# poe.net
KiCad netlist of a schematic drawn in Altium Designer
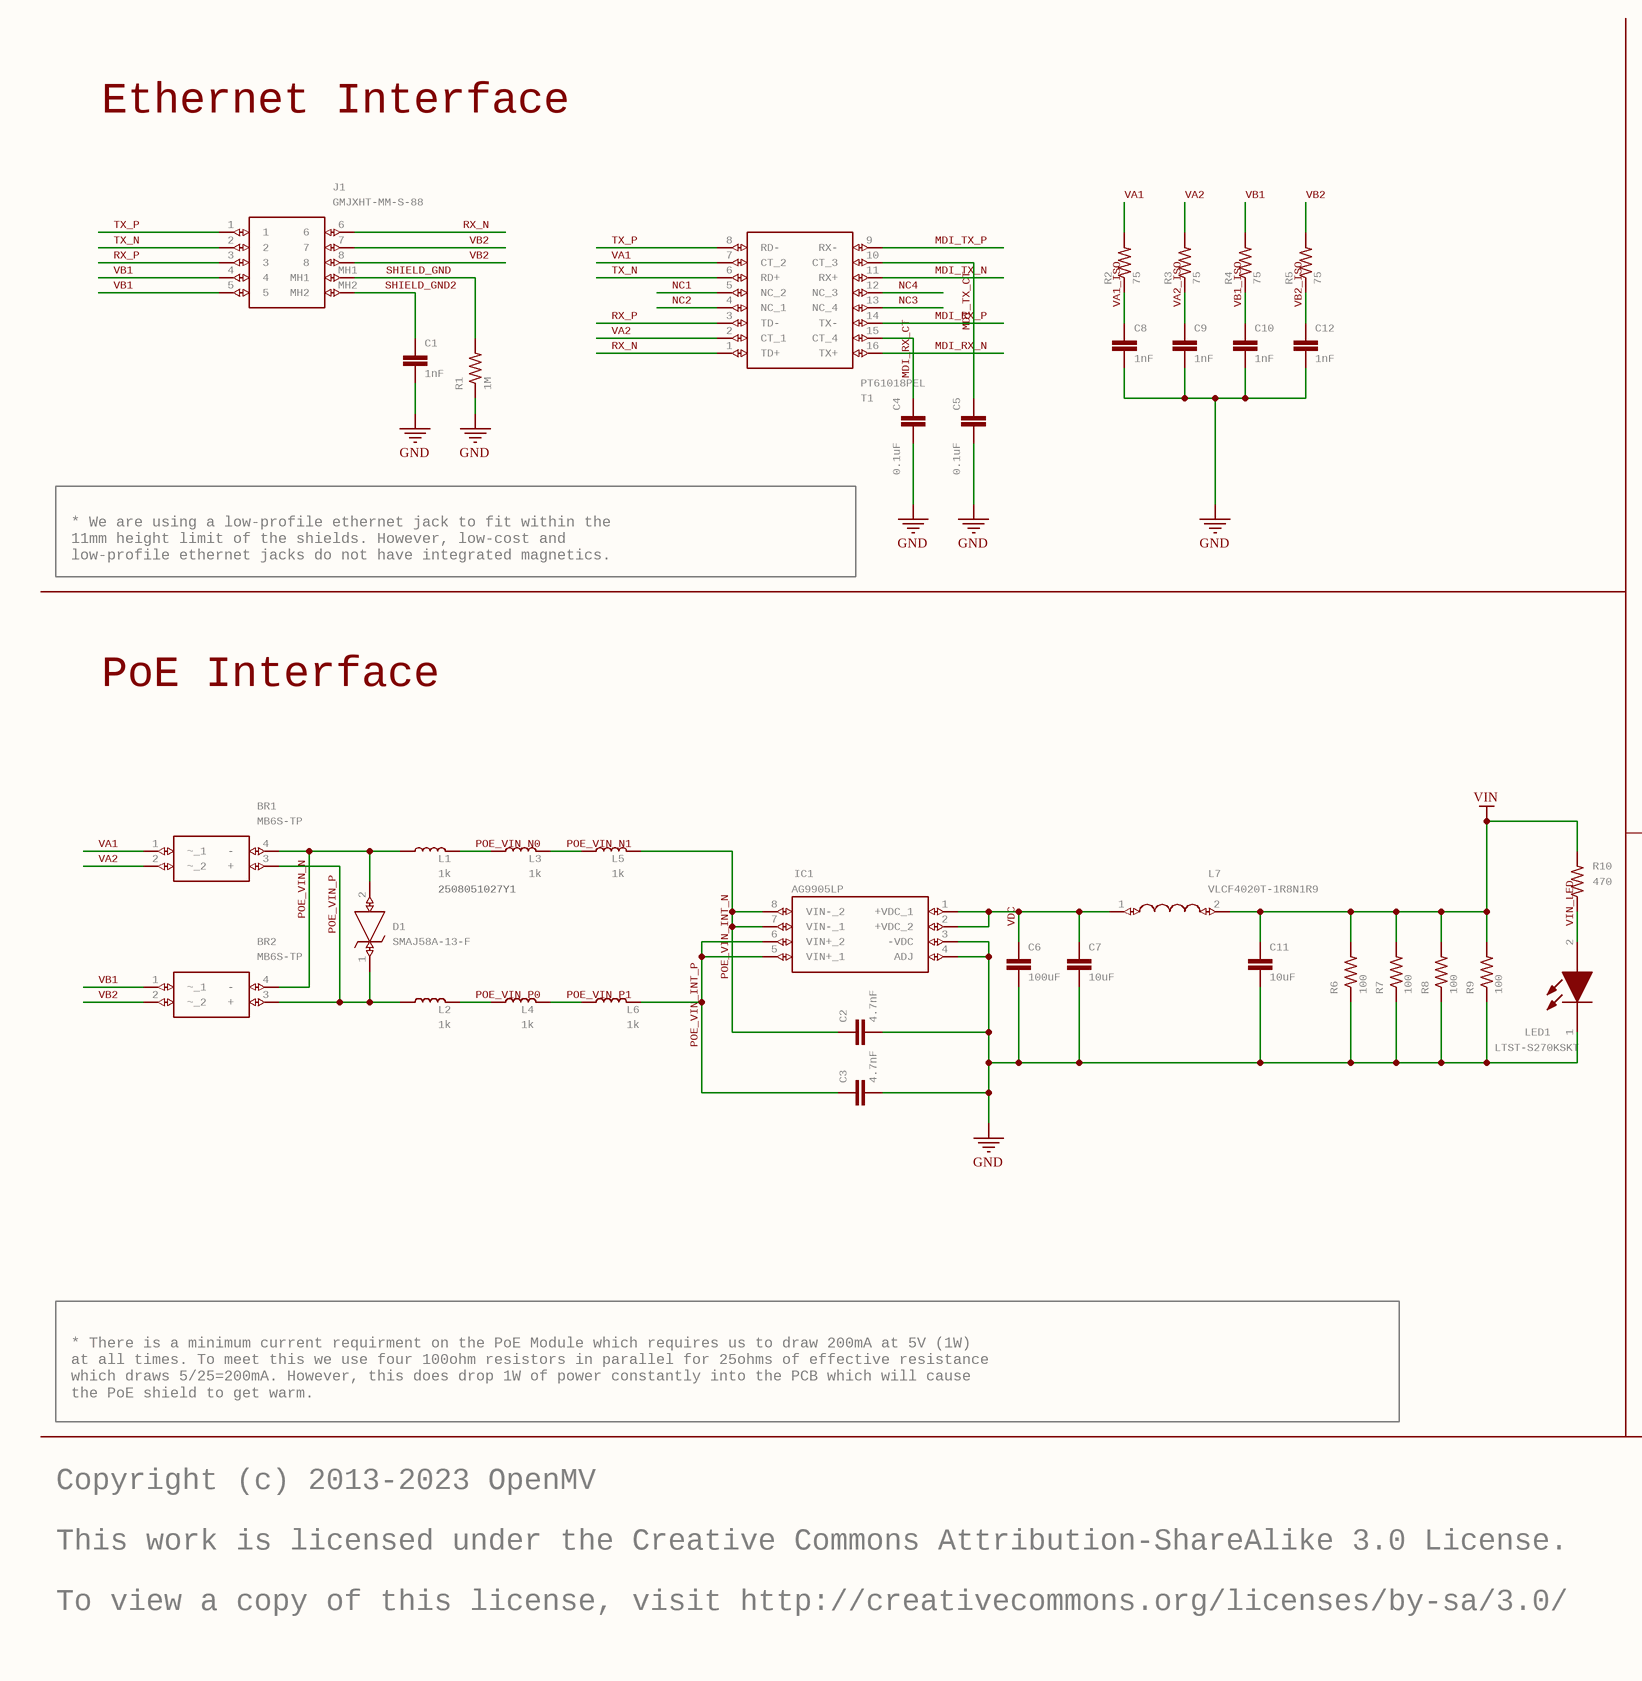
[diagram p0: poe.SchDoc, left]
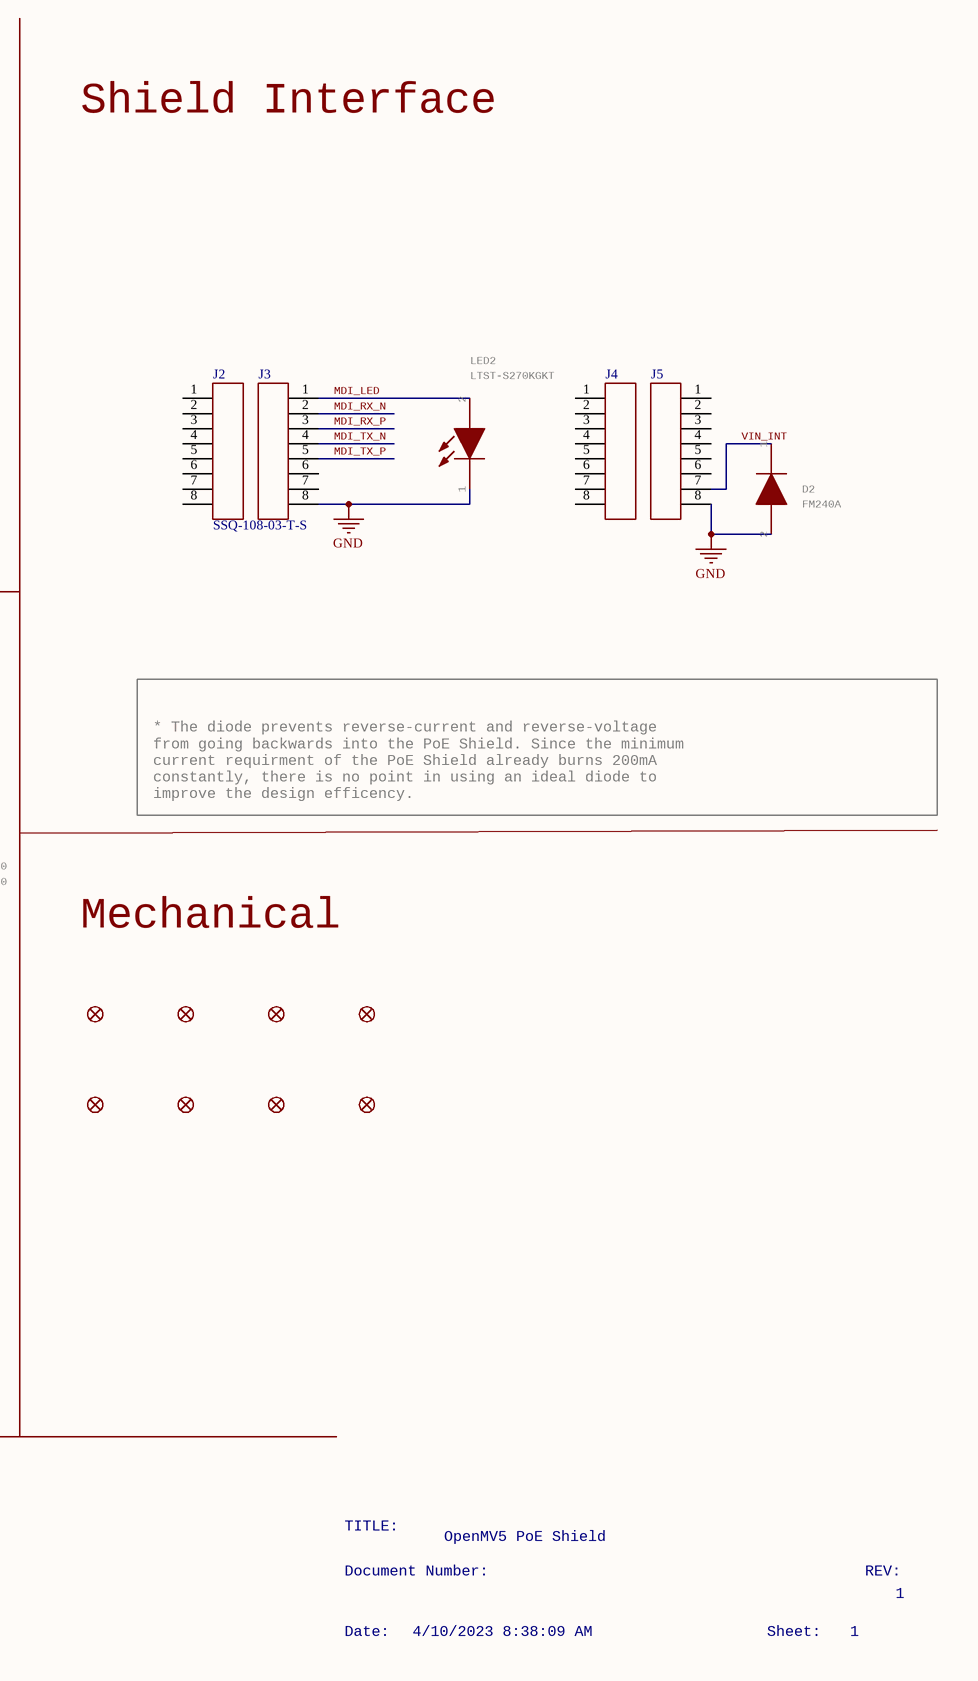
[diagram p1: poe.SchDoc, right]

(export (version "E")
  (design (tool "Eeschema 10.0.6"))
  (components
    (comp (ref "BR1")
      (value "MB6S-TP")
      (footprint "SOP254P665X270-4N")
      (description "MICRO COMMERCIAL COMPONENTS - MB6S-TP - BRIDGE RECTIFIER, 500mA, 600V   Source:  Datasheet")
      (fields (field (name "MOUSER_PART_NUMBER") "833-MB6S-TP"))
      (libsource (lib "poe") (part "MB6S-TP"))
    )
    (comp (ref "BR2")
      (value "MB6S-TP")
      (footprint "SOP254P665X270-4N")
      (description "MICRO COMMERCIAL COMPONENTS - MB6S-TP - BRIDGE RECTIFIER, 500mA, 600V   Source:  Datasheet")
      (fields (field (name "MOUSER_PART_NUMBER") "833-MB6S-TP"))
      (libsource (lib "poe") (part "MB6S-TP"))
    )
    (comp (ref "C1")
      (value "1nF")
      (footprint "C1206")
      (description "CAPACITOR, European symbol")
      (fields (field (name "MPN") "1206B102K252CT"))
      (libsource (lib "poe") (part "C-EUC1206"))
    )
    (comp (ref "C2")
      (value "4.7nF")
      (footprint "C1812")
      (description "CAPACITOR, European symbol")
      (fields (field (name "MPN") "202S43W472KV4E"))
      (libsource (lib "poe") (part "C-EUC1812"))
    )
    (comp (ref "C3")
      (value "4.7nF")
      (footprint "C1812")
      (description "CAPACITOR, European symbol")
      (fields (field (name "MPN") "202S43W472KV4E"))
      (libsource (lib "poe") (part "C-EUC1812"))
    )
    (comp (ref "C4")
      (value "0.1uF")
      (footprint "C0402")
      (description "CAPACITOR, European symbol")
      (fields (field (name "MPN") "GRM155R71H104KE14D"))
      (libsource (lib "poe") (part "C-EUC0201"))
    )
    (comp (ref "C5")
      (value "0.1uF")
      (footprint "C0402")
      (description "CAPACITOR, European symbol")
      (fields (field (name "MPN") "GRM155R71H104KE14D"))
      (libsource (lib "poe") (part "C-EUC0201"))
    )
    (comp (ref "C6")
      (value "100uF")
      (footprint "C1206")
      (description "CAPACITOR, European symbol")
      (fields (field (name "MPN") "CL31A107MQHNNWE"))
      (libsource (lib "poe") (part "C-EUC1206"))
    )
    (comp (ref "C7")
      (value "10uF")
      (footprint "C0402")
      (description "CAPACITOR, European symbol")
      (fields (field (name "MPN") "GRM155R60J106ME05D"))
      (libsource (lib "poe") (part "C-EUC0402"))
    )
    (comp (ref "C8")
      (value "1nF")
      (footprint "C1206")
      (description "CAPACITOR, European symbol")
      (fields (field (name "MPN") "1206B102K252CT"))
      (libsource (lib "poe") (part "C-EUC1206"))
    )
    (comp (ref "C9")
      (value "1nF")
      (footprint "C1206")
      (description "CAPACITOR, European symbol")
      (fields (field (name "MPN") "1206B102K252CT"))
      (libsource (lib "poe") (part "C-EUC1206"))
    )
    (comp (ref "C10")
      (value "1nF")
      (footprint "C1206")
      (description "CAPACITOR, European symbol")
      (fields (field (name "MPN") "1206B102K252CT"))
      (libsource (lib "poe") (part "C-EUC1206"))
    )
    (comp (ref "C11")
      (value "10uF")
      (footprint "C0402")
      (description "CAPACITOR, European symbol")
      (fields (field (name "MPN") "GRM155R60J106ME05D"))
      (libsource (lib "poe") (part "C-EUC0402"))
    )
    (comp (ref "C12")
      (value "1nF")
      (footprint "C1206")
      (description "CAPACITOR, European symbol")
      (fields (field (name "MPN") "1206B102K252CT"))
      (libsource (lib "poe") (part "C-EUC1206"))
    )
    (comp (ref "D1")
      (value "SMAJ58A-13-F")
      (footprint "DIOM5226X230N")
      (description "Diodes Inc SMAJ58A-13-F, Uni-Directional TVS Diode, 400W, 2-Pin DO-214AC   Source:  Datasheet")
      (fields (field (name "MOUSER_PART_NUMBER") "621-SMAJ58A-13-F") (field (name "MPN") "SMAJ58A/TR13"))
      (libsource (lib "poe") (part "SMAJ58A-13-F"))
    )
    (comp (ref "D2")
      (value "FM240A")
      (footprint "DIOM5025X231N")
      (description "Diodes - General Purpose, Power, Switching GP Si Rectifier SMB,2A,40V   Source:  Datasheet")
      (fields (field (name "MOUSER_PART_NUMBER") "583-FM240A"))
      (libsource (lib "poe") (part "FM240A"))
    )
    (comp (ref "FD1")
      (value "FIDUCIAL1X2")
      (footprint "FIDUCIAL-1X2")
      (fields (field (name "LIBRARYNAME") "SparkFun-Aesthetics"))
      (libsource (lib "poe") (part "FIDUCIAL1X2"))
    )
    (comp (ref "FD2")
      (value "FIDUCIAL1X2")
      (footprint "FIDUCIAL-1X2")
      (fields (field (name "LIBRARYNAME") "SparkFun-Aesthetics"))
      (libsource (lib "poe") (part "FIDUCIAL1X2"))
    )
    (comp (ref "FD3")
      (value "FIDUCIAL1X2")
      (footprint "FIDUCIAL-1X2")
      (fields (field (name "LIBRARYNAME") "SparkFun-Aesthetics"))
      (libsource (lib "poe") (part "FIDUCIAL1X2"))
    )
    (comp (ref "FD4")
      (value "FIDUCIAL1X2")
      (footprint "FIDUCIAL-1X2")
      (fields (field (name "LIBRARYNAME") "SparkFun-Aesthetics"))
      (libsource (lib "poe") (part "FIDUCIAL1X2"))
    )
    (comp (ref "FD5")
      (value "FIDUCIAL1X2")
      (footprint "FIDUCIAL-1X2")
      (fields (field (name "LIBRARYNAME") "SparkFun-Aesthetics"))
      (libsource (lib "poe") (part "FIDUCIAL1X2"))
    )
    (comp (ref "FD6")
      (value "FIDUCIAL1X2")
      (footprint "FIDUCIAL-1X2")
      (fields (field (name "LIBRARYNAME") "SparkFun-Aesthetics"))
      (libsource (lib "poe") (part "FIDUCIAL1X2"))
    )
    (comp (ref "FD7")
      (value "FIDUCIAL1X2")
      (footprint "FIDUCIAL-1X2")
      (fields (field (name "LIBRARYNAME") "SparkFun-Aesthetics"))
      (libsource (lib "poe") (part "FIDUCIAL1X2"))
    )
    (comp (ref "FD8")
      (value "FIDUCIAL1X2")
      (footprint "FIDUCIAL-1X2")
      (fields (field (name "LIBRARYNAME") "SparkFun-Aesthetics"))
      (libsource (lib "poe") (part "FIDUCIAL1X2"))
    )
    (comp (ref "IC1")
      (value "AG9905LP")
      (footprint "AG9905LP")
      (description "Power Management Modules IEEE802.3af PD module. 5V 7W, low profile   Source:  Datasheet")
      (fields
        (field (name "MANUFACTURER_PART_NUMBER") "Ag9905LP")
        (field (name "MOUSER_PART_NUMBER") "480-AG9905LP")
      )
      (libsource (lib "poe") (part "AG9905LP"))
    )
    (comp (ref "J1")
      (value "GMJXHT-MM-S-88")
      (footprint "GMJXHTMMS88")
      (description "MODJACK MIDMOUNT 8P8C SHIELD RoHS COMPLIANT   Source:  Datasheet")
      (fields (field (name "MOUSER_PART_NUMBER") "806-GMJXHT-MM-S-88"))
      (libsource (lib "poe") (part "GMJXHT-MM-S-88"))
    )
    (comp (ref "J2") (value "SSQ-108-03-T-S") (footprint "HDR_1X8") (libsource (lib "") (part "HDR_1X8_1")))
    (comp (ref "J3") (value "SSQ-108-03-T-S") (footprint "HDR_1X8") (libsource (lib "pir") (part "HDR_1X8")))
    (comp (ref "J4") (value "SSQ-108-03-T-S") (footprint "HDR_1X8") (libsource (lib "") (part "HDR_1X8_1")))
    (comp (ref "J5") (value "SSQ-108-03-T-S") (footprint "HDR_1X8") (libsource (lib "pir") (part "HDR_1X8")))
    (comp (ref "L1")
      (value "1k")
      (footprint "R0805")
      (fields
        (field (name "MPN") "2508051027Y1")
        (field (name "PART NUMBER") "2508051027Y1")
        (field (name "LIBRARYNAME") "SparkFun-Coils")
      )
      (libsource (lib "poe") (part "INDUCTOR-0402-3.9NH"))
    )
    (comp (ref "L2")
      (value "1k")
      (footprint "R0805")
      (fields (field (name "MPN") "2508051027Y1") (field (name "LIBRARYNAME") "SparkFun-Coils"))
      (libsource (lib "poe") (part "INDUCTOR-0402-3.9NH"))
    )
    (comp (ref "L3")
      (value "1k")
      (footprint "R0805")
      (fields (field (name "MPN") "2508051027Y1") (field (name "LIBRARYNAME") "SparkFun-Coils"))
      (libsource (lib "poe") (part "INDUCTOR-0402-3.9NH"))
    )
    (comp (ref "L4")
      (value "1k")
      (footprint "R0805")
      (fields (field (name "MPN") "2508051027Y1") (field (name "LIBRARYNAME") "SparkFun-Coils"))
      (libsource (lib "poe") (part "INDUCTOR-0402-3.9NH"))
    )
    (comp (ref "L5")
      (value "1k")
      (footprint "R0805")
      (fields (field (name "MPN") "2508051027Y1") (field (name "LIBRARYNAME") "SparkFun-Coils"))
      (libsource (lib "poe") (part "INDUCTOR-0402-3.9NH"))
    )
    (comp (ref "L6")
      (value "1k")
      (footprint "R0805")
      (fields (field (name "MPN") "2508051027Y1") (field (name "LIBRARYNAME") "SparkFun-Coils"))
      (libsource (lib "poe") (part "INDUCTOR-0402-3.9NH"))
    )
    (comp (ref "L7")
      (value "VLCF4020T-1R8N1R9")
      (footprint "VLCF4020T-1R8N1R9")
      (description "Power Inductors - SMD 1.8uH 1.9A 4x4x2.0mm")
      (libsource (lib "poe") (part "NR6045T1R8N"))
    )
    (comp (ref "LED1")
      (value "LTST-S270KSKT")
      (footprint "LTSTS270K")
      (fields (field (name "MOUSER_PART_NUMBER") "859-LTST-S270KSKT"))
      (libsource (lib "poe") (part "LTST-S270KSKT"))
    )
    (comp (ref "LED2")
      (value "LTST-S270KGKT")
      (footprint "LTSTS270K")
      (fields (field (name "MOUSER_PART_NUMBER") "859-LTST-S270KGKT"))
      (libsource (lib "poe") (part "LTST-S270KGKT"))
    )
    (comp (ref "R1")
      (value "1M")
      (footprint "R1206")
      (description "RESISTOR, American symbol")
      (fields (field (name "MPN") "RMCF1206FT1M00"))
      (libsource (lib "poe") (part "R-US_R1206"))
    )
    (comp (ref "R2")
      (value "75")
      (footprint "R0402")
      (description "RESISTOR, American symbol")
      (fields (field (name "MPN") "CR0402-FX-75R0GLF"))
      (libsource (lib "poe") (part "R-US_R0402"))
    )
    (comp (ref "R3")
      (value "75")
      (footprint "R0402")
      (description "RESISTOR, American symbol")
      (fields (field (name "MPN") "CR0402-FX-75R0GLF"))
      (libsource (lib "poe") (part "R-US_R0402"))
    )
    (comp (ref "R4")
      (value "75")
      (footprint "R0402")
      (description "RESISTOR, American symbol")
      (fields (field (name "MPN") "CR0402-FX-75R0GLF"))
      (libsource (lib "poe") (part "R-US_R0402"))
    )
    (comp (ref "R5")
      (value "75")
      (footprint "R0402")
      (description "RESISTOR, American symbol")
      (fields (field (name "MPN") "CR0402-FX-75R0GLF"))
      (libsource (lib "poe") (part "R-US_R0402"))
    )
    (comp (ref "R6")
      (value "100")
      (footprint "R2512")
      (description "RESISTOR, American symbol")
      (fields (field (name "MPN") "RC2512JK-07100RL"))
      (libsource (lib "poe") (part "R-US_R2512"))
    )
    (comp (ref "R7")
      (value "100")
      (footprint "R2512")
      (description "RESISTOR, American symbol")
      (fields (field (name "MPN") "RC2512JK-07100RL"))
      (libsource (lib "poe") (part "R-US_R2512"))
    )
    (comp (ref "R8")
      (value "100")
      (footprint "R2512")
      (description "RESISTOR, American symbol")
      (fields (field (name "MPN") "RC2512JK-07100RL"))
      (libsource (lib "poe") (part "R-US_R2512"))
    )
    (comp (ref "R9")
      (value "100")
      (footprint "R2512")
      (description "RESISTOR, American symbol")
      (fields (field (name "MPN") "RC2512JK-07100RL"))
      (libsource (lib "poe") (part "R-US_R2512"))
    )
    (comp (ref "R10")
      (value "470")
      (footprint "R0603")
      (description "RESISTOR, American symbol")
      (fields (field (name "MPN") "CR0603-FX-4700ELF"))
      (libsource (lib "poe") (part "R-US_R0603"))
    )
    (comp (ref "T1")
      (value "PT61018PEL")
      (footprint "SOIC127P930X565-16N")
      (description "BOURNS - PT61018PEL - TRANSFORMER, LAN, 1CT:1CT, 350UH, SMD   Source:  Datasheet")
      (fields (field (name "MOUSER_PART_NUMBER") "652-PT61018PEL"))
      (libsource (lib "poe") (part "PT61018PEL"))
    )
  )
  (nets
    (net (code "1") (name "/MDI_LED") (class "Default")
      (node (ref "J3") (pin "1") (pintype "passive"))
      (node (ref "LED2") (pin "2") (pinfunction "A_2") (pintype "bidirectional"))
    )
    (net (code "2") (name "/MDI_RX_CT") (class "Default")
      (node (ref "C4") (pin "1") (pinfunction "1_1") (pintype "passive"))
      (node (ref "T1") (pin "15") (pinfunction "CT_4_15") (pintype "bidirectional"))
    )
    (net (code "3") (name "/MDI_RX_N") (class "Default")
      (node (ref "J3") (pin "2") (pintype "passive"))
      (node (ref "T1") (pin "16") (pinfunction "TX+_16") (pintype "bidirectional"))
    )
    (net (code "4") (name "/MDI_RX_P") (class "Default")
      (node (ref "J3") (pin "3") (pintype "passive"))
      (node (ref "T1") (pin "14") (pinfunction "TX-_14") (pintype "bidirectional"))
    )
    (net (code "5") (name "/MDI_TX_CT") (class "Default")
      (node (ref "C5") (pin "1") (pinfunction "1_1") (pintype "passive"))
      (node (ref "T1") (pin "10") (pinfunction "CT_3_10") (pintype "bidirectional"))
    )
    (net (code "6") (name "/MDI_TX_N") (class "Default")
      (node (ref "J3") (pin "4") (pintype "passive"))
      (node (ref "T1") (pin "11") (pinfunction "RX+_11") (pintype "bidirectional"))
    )
    (net (code "7") (name "/MDI_TX_P") (class "Default")
      (node (ref "J3") (pin "5") (pintype "passive"))
      (node (ref "T1") (pin "9") (pinfunction "RX-_9") (pintype "bidirectional"))
    )
    (net (code "8") (name "/NC1") (class "Default")
      (node (ref "T1") (pin "5") (pinfunction "NC_2_5") (pintype "bidirectional"))
    )
    (net (code "9") (name "/NC2") (class "Default")
      (node (ref "T1") (pin "4") (pinfunction "NC_1_4") (pintype "bidirectional"))
    )
    (net (code "10") (name "/NC3") (class "Default")
      (node (ref "T1") (pin "13") (pinfunction "NC_4_13") (pintype "bidirectional"))
    )
    (net (code "11") (name "/NC4") (class "Default")
      (node (ref "T1") (pin "12") (pinfunction "NC_3_12") (pintype "bidirectional"))
    )
    (net (code "12") (name "/POE_VIN_INT_N") (class "Default")
      (node (ref "C2") (pin "1") (pinfunction "1_1") (pintype "passive"))
      (node (ref "IC1") (pin "7") (pinfunction "VIN-_1_7") (pintype "bidirectional"))
      (node (ref "IC1") (pin "8") (pinfunction "VIN-_2_8") (pintype "bidirectional"))
      (node (ref "L5") (pin "2") (pinfunction "2_2") (pintype "passive"))
    )
    (net (code "13") (name "/POE_VIN_INT_P") (class "Default")
      (node (ref "C3") (pin "1") (pinfunction "1_1") (pintype "passive"))
      (node (ref "IC1") (pin "5") (pinfunction "VIN+_1_5") (pintype "bidirectional"))
      (node (ref "IC1") (pin "6") (pinfunction "VIN+_2_6") (pintype "bidirectional"))
      (node (ref "L6") (pin "2") (pinfunction "2_2") (pintype "passive"))
    )
    (net (code "14") (name "/POE_VIN_N") (class "Default")
      (node (ref "BR1") (pin "4") (pinfunction "-_4") (pintype "bidirectional"))
      (node (ref "BR2") (pin "4") (pinfunction "-_4") (pintype "bidirectional"))
      (node (ref "D1") (pin "2") (pinfunction "A_2") (pintype "bidirectional"))
      (node (ref "L1") (pin "1") (pinfunction "1_1") (pintype "passive"))
    )
    (net (code "15") (name "/POE_VIN_N0") (class "Default")
      (node (ref "L1") (pin "2") (pinfunction "2_2") (pintype "passive"))
      (node (ref "L3") (pin "1") (pinfunction "1_1") (pintype "passive"))
    )
    (net (code "16") (name "/POE_VIN_N1") (class "Default")
      (node (ref "L3") (pin "2") (pinfunction "2_2") (pintype "passive"))
      (node (ref "L5") (pin "1") (pinfunction "1_1") (pintype "passive"))
    )
    (net (code "17") (name "/POE_VIN_P") (class "Default")
      (node (ref "BR1") (pin "3") (pinfunction "+_3") (pintype "bidirectional"))
      (node (ref "BR2") (pin "3") (pinfunction "+_3") (pintype "bidirectional"))
      (node (ref "D1") (pin "1") (pinfunction "K_1") (pintype "bidirectional"))
      (node (ref "L2") (pin "1") (pinfunction "1_1") (pintype "passive"))
    )
    (net (code "18") (name "/POE_VIN_P0") (class "Default")
      (node (ref "L2") (pin "2") (pinfunction "2_2") (pintype "passive"))
      (node (ref "L4") (pin "1") (pinfunction "1_1") (pintype "passive"))
    )
    (net (code "19") (name "/POE_VIN_P1") (class "Default")
      (node (ref "L4") (pin "2") (pinfunction "2_2") (pintype "passive"))
      (node (ref "L6") (pin "1") (pinfunction "1_1") (pintype "passive"))
    )
    (net (code "20") (name "/RX_N") (class "Default")
      (node (ref "J1") (pin "6") (pinfunction "6_6") (pintype "bidirectional"))
      (node (ref "T1") (pin "1") (pinfunction "TD+_1") (pintype "bidirectional"))
    )
    (net (code "21") (name "/RX_P") (class "Default")
      (node (ref "J1") (pin "3") (pinfunction "3_3") (pintype "bidirectional"))
      (node (ref "T1") (pin "3") (pinfunction "TD-_3") (pintype "bidirectional"))
    )
    (net (code "22") (name "/SHIELD_GND") (class "Default")
      (node (ref "J1") (pin "MH1") (pinfunction "MH1_MH1") (pintype "bidirectional"))
      (node (ref "R1") (pin "2") (pinfunction "2_2") (pintype "passive"))
    )
    (net (code "23") (name "/SHIELD_GND2") (class "Default")
      (node (ref "C1") (pin "1") (pinfunction "1_1") (pintype "passive"))
      (node (ref "J1") (pin "MH2") (pinfunction "MH2_MH2") (pintype "bidirectional"))
    )
    (net (code "24") (name "/TX_N") (class "Default")
      (node (ref "J1") (pin "2") (pinfunction "2_2") (pintype "bidirectional"))
      (node (ref "T1") (pin "6") (pinfunction "RD+_6") (pintype "bidirectional"))
    )
    (net (code "25") (name "/TX_P") (class "Default")
      (node (ref "J1") (pin "1") (pinfunction "1_1") (pintype "bidirectional"))
      (node (ref "T1") (pin "8") (pinfunction "RD-_8") (pintype "bidirectional"))
    )
    (net (code "26") (name "/VA1") (class "Default")
      (node (ref "BR1") (pin "1") (pinfunction "~_1_1") (pintype "bidirectional"))
      (node (ref "R2") (pin "2") (pinfunction "2_2") (pintype "passive"))
      (node (ref "T1") (pin "7") (pinfunction "CT_2_7") (pintype "bidirectional"))
    )
    (net (code "27") (name "/VA1_ISO") (class "Default")
      (node (ref "C8") (pin "1") (pinfunction "1_1") (pintype "passive"))
      (node (ref "R2") (pin "1") (pinfunction "1_1") (pintype "passive"))
    )
    (net (code "28") (name "/VA2") (class "Default")
      (node (ref "BR1") (pin "2") (pinfunction "~_2_2") (pintype "bidirectional"))
      (node (ref "R3") (pin "2") (pinfunction "2_2") (pintype "passive"))
      (node (ref "T1") (pin "2") (pinfunction "CT_1_2") (pintype "bidirectional"))
    )
    (net (code "29") (name "/VA2_ISO") (class "Default")
      (node (ref "C9") (pin "1") (pinfunction "1_1") (pintype "passive"))
      (node (ref "R3") (pin "1") (pinfunction "1_1") (pintype "passive"))
    )
    (net (code "30") (name "/VB1") (class "Default")
      (node (ref "BR2") (pin "1") (pinfunction "~_1_1") (pintype "bidirectional"))
      (node (ref "J1") (pin "4") (pinfunction "4_4") (pintype "bidirectional"))
      (node (ref "J1") (pin "5") (pinfunction "5_5") (pintype "bidirectional"))
      (node (ref "R4") (pin "2") (pinfunction "2_2") (pintype "passive"))
    )
    (net (code "31") (name "/VB1_ISO") (class "Default")
      (node (ref "C10") (pin "1") (pinfunction "1_1") (pintype "passive"))
      (node (ref "R4") (pin "1") (pinfunction "1_1") (pintype "passive"))
    )
    (net (code "32") (name "/VB2") (class "Default")
      (node (ref "BR2") (pin "2") (pinfunction "~_2_2") (pintype "bidirectional"))
      (node (ref "J1") (pin "7") (pinfunction "7_7") (pintype "bidirectional"))
      (node (ref "J1") (pin "8") (pinfunction "8_8") (pintype "bidirectional"))
      (node (ref "R5") (pin "2") (pinfunction "2_2") (pintype "passive"))
    )
    (net (code "33") (name "/VB2_ISO") (class "Default")
      (node (ref "C12") (pin "1") (pinfunction "1_1") (pintype "passive"))
      (node (ref "R5") (pin "1") (pinfunction "1_1") (pintype "passive"))
    )
    (net (code "34") (name "/VDC") (class "Default")
      (node (ref "C6") (pin "1") (pinfunction "1_1") (pintype "passive"))
      (node (ref "C7") (pin "1") (pinfunction "1_1") (pintype "passive"))
      (node (ref "IC1") (pin "1") (pinfunction "+VDC_1_1") (pintype "bidirectional"))
      (node (ref "IC1") (pin "2") (pinfunction "+VDC_2_2") (pintype "bidirectional"))
      (node (ref "L7") (pin "1") (pinfunction "1_1") (pintype "bidirectional"))
    )
    (net (code "35") (name "/VIN_INT") (class "Default")
      (node (ref "D2") (pin "1") (pinfunction "K_1") (pintype "bidirectional"))
      (node (ref "J5") (pin "7") (pintype "passive"))
    )
    (net (code "36") (name "/VIN_LED") (class "Default")
      (node (ref "LED1") (pin "2") (pinfunction "A_2") (pintype "bidirectional"))
      (node (ref "R10") (pin "1") (pinfunction "1_1") (pintype "passive"))
    )
    (net (code "37") (name "GND") (class "Default")
      (node (ref "C1") (pin "2") (pinfunction "2_2") (pintype "passive"))
      (node (ref "C10") (pin "2") (pinfunction "2_2") (pintype "passive"))
      (node (ref "C11") (pin "2") (pinfunction "2_2") (pintype "passive"))
      (node (ref "C12") (pin "2") (pinfunction "2_2") (pintype "passive"))
      (node (ref "C2") (pin "2") (pinfunction "2_2") (pintype "passive"))
      (node (ref "C3") (pin "2") (pinfunction "2_2") (pintype "passive"))
      (node (ref "C4") (pin "2") (pinfunction "2_2") (pintype "passive"))
      (node (ref "C5") (pin "2") (pinfunction "2_2") (pintype "passive"))
      (node (ref "C6") (pin "2") (pinfunction "2_2") (pintype "passive"))
      (node (ref "C7") (pin "2") (pinfunction "2_2") (pintype "passive"))
      (node (ref "C8") (pin "2") (pinfunction "2_2") (pintype "passive"))
      (node (ref "C9") (pin "2") (pinfunction "2_2") (pintype "passive"))
      (node (ref "D2") (pin "2") (pinfunction "A_2") (pintype "bidirectional"))
      (node (ref "IC1") (pin "3") (pinfunction "-VDC_3") (pintype "bidirectional"))
      (node (ref "IC1") (pin "4") (pinfunction "ADJ_4") (pintype "bidirectional"))
      (node (ref "J3") (pin "8") (pintype "passive"))
      (node (ref "J5") (pin "8") (pintype "passive"))
      (node (ref "LED1") (pin "1") (pinfunction "K_1") (pintype "bidirectional"))
      (node (ref "LED2") (pin "1") (pinfunction "K_1") (pintype "bidirectional"))
      (node (ref "R1") (pin "1") (pinfunction "1_1") (pintype "passive"))
      (node (ref "R6") (pin "1") (pinfunction "1_1") (pintype "passive"))
      (node (ref "R7") (pin "1") (pinfunction "1_1") (pintype "passive"))
      (node (ref "R8") (pin "1") (pinfunction "1_1") (pintype "passive"))
      (node (ref "R9") (pin "1") (pinfunction "1_1") (pintype "passive"))
    )
    (net (code "38") (name "VIN") (class "Default")
      (node (ref "C11") (pin "1") (pinfunction "1_1") (pintype "passive"))
      (node (ref "L7") (pin "2") (pinfunction "2_2") (pintype "bidirectional"))
      (node (ref "R10") (pin "2") (pinfunction "2_2") (pintype "passive"))
      (node (ref "R6") (pin "2") (pinfunction "2_2") (pintype "passive"))
      (node (ref "R7") (pin "2") (pinfunction "2_2") (pintype "passive"))
      (node (ref "R8") (pin "2") (pinfunction "2_2") (pintype "passive"))
      (node (ref "R9") (pin "2") (pinfunction "2_2") (pintype "passive"))
    )
    (net (code "39") (name "unconnected-(J2-Pad1)") (class "Default")
      (node (ref "J2") (pin "1") (pintype "passive"))
    )
    (net (code "40") (name "unconnected-(J2-Pad2)") (class "Default")
      (node (ref "J2") (pin "2") (pintype "passive"))
    )
    (net (code "41") (name "unconnected-(J2-Pad3)") (class "Default")
      (node (ref "J2") (pin "3") (pintype "passive"))
    )
    (net (code "42") (name "unconnected-(J2-Pad4)") (class "Default")
      (node (ref "J2") (pin "4") (pintype "passive"))
    )
    (net (code "43") (name "unconnected-(J2-Pad5)") (class "Default")
      (node (ref "J2") (pin "5") (pintype "passive"))
    )
    (net (code "44") (name "unconnected-(J2-Pad6)") (class "Default")
      (node (ref "J2") (pin "6") (pintype "passive"))
    )
    (net (code "45") (name "unconnected-(J2-Pad7)") (class "Default")
      (node (ref "J2") (pin "7") (pintype "passive"))
    )
    (net (code "46") (name "unconnected-(J2-Pad8)") (class "Default")
      (node (ref "J2") (pin "8") (pintype "passive"))
    )
    (net (code "47") (name "unconnected-(J3-Pad6)") (class "Default")
      (node (ref "J3") (pin "6") (pintype "passive"))
    )
    (net (code "48") (name "unconnected-(J3-Pad7)") (class "Default")
      (node (ref "J3") (pin "7") (pintype "passive"))
    )
    (net (code "49") (name "unconnected-(J4-Pad1)") (class "Default")
      (node (ref "J4") (pin "1") (pintype "passive"))
    )
    (net (code "50") (name "unconnected-(J4-Pad2)") (class "Default")
      (node (ref "J4") (pin "2") (pintype "passive"))
    )
    (net (code "51") (name "unconnected-(J4-Pad3)") (class "Default")
      (node (ref "J4") (pin "3") (pintype "passive"))
    )
    (net (code "52") (name "unconnected-(J4-Pad4)") (class "Default")
      (node (ref "J4") (pin "4") (pintype "passive"))
    )
    (net (code "53") (name "unconnected-(J4-Pad5)") (class "Default")
      (node (ref "J4") (pin "5") (pintype "passive"))
    )
    (net (code "54") (name "unconnected-(J4-Pad6)") (class "Default")
      (node (ref "J4") (pin "6") (pintype "passive"))
    )
    (net (code "55") (name "unconnected-(J4-Pad7)") (class "Default")
      (node (ref "J4") (pin "7") (pintype "passive"))
    )
    (net (code "56") (name "unconnected-(J4-Pad8)") (class "Default")
      (node (ref "J4") (pin "8") (pintype "passive"))
    )
    (net (code "57") (name "unconnected-(J5-Pad1)") (class "Default")
      (node (ref "J5") (pin "1") (pintype "passive"))
    )
    (net (code "58") (name "unconnected-(J5-Pad2)") (class "Default")
      (node (ref "J5") (pin "2") (pintype "passive"))
    )
    (net (code "59") (name "unconnected-(J5-Pad3)") (class "Default")
      (node (ref "J5") (pin "3") (pintype "passive"))
    )
    (net (code "60") (name "unconnected-(J5-Pad4)") (class "Default")
      (node (ref "J5") (pin "4") (pintype "passive"))
    )
    (net (code "61") (name "unconnected-(J5-Pad5)") (class "Default")
      (node (ref "J5") (pin "5") (pintype "passive"))
    )
    (net (code "62") (name "unconnected-(J5-Pad6)") (class "Default")
      (node (ref "J5") (pin "6") (pintype "passive"))
    )
  )
)
